# dual-dac-w-32-ch-sh-DAC-BOARD.net
KiCad netlist of a schematic drawn in EAGLE
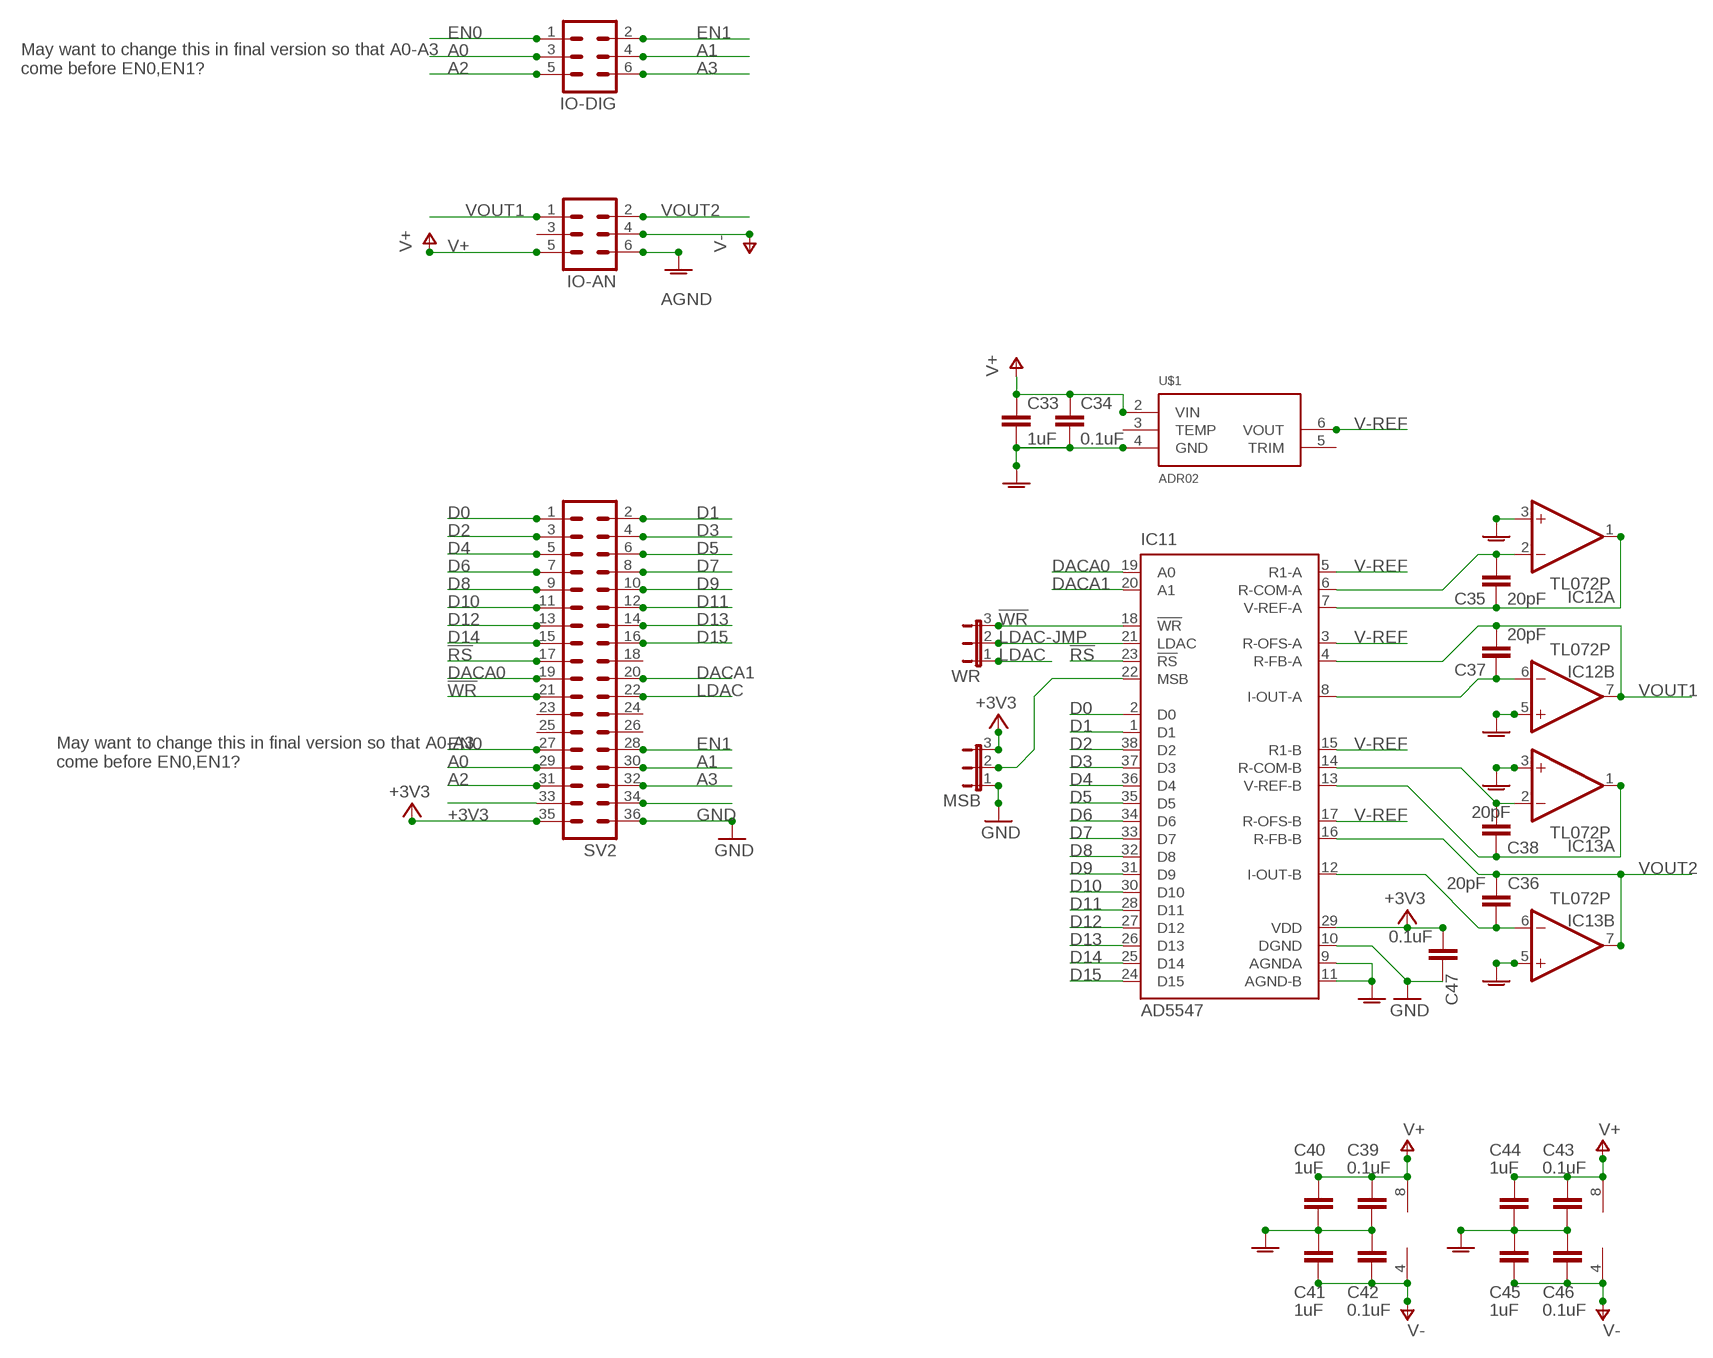
[diagram p0: schematic, sheet 1]

(export (version "E")
  (design (tool "Eeschema 10.0.6"))
  (components
    (comp (ref "C33")
      (value "1uF")
      (footprint "eagle-import:C0603")
      (libsource (lib "eagle-import") (part "C-EUC0603"))
    )
    (comp (ref "C34")
      (value "0.1uF")
      (footprint "eagle-import:C0603")
      (libsource (lib "eagle-import") (part "C-EUC0603"))
    )
    (comp (ref "C35")
      (value "20pF")
      (footprint "eagle-import:C0603")
      (libsource (lib "eagle-import") (part "C-EUC0603"))
    )
    (comp (ref "C36")
      (value "20pF")
      (footprint "eagle-import:C0603")
      (libsource (lib "eagle-import") (part "C-EUC0603"))
    )
    (comp (ref "C37")
      (value "20pF")
      (footprint "eagle-import:C0603")
      (libsource (lib "eagle-import") (part "C-EUC0603"))
    )
    (comp (ref "C38")
      (value "20pF")
      (footprint "eagle-import:C0603")
      (libsource (lib "eagle-import") (part "C-EUC0603"))
    )
    (comp (ref "C39")
      (value "0.1uF")
      (footprint "eagle-import:C0603")
      (libsource (lib "eagle-import") (part "C-EUC0603"))
    )
    (comp (ref "C40")
      (value "1uF")
      (footprint "eagle-import:C0603")
      (libsource (lib "eagle-import") (part "C-EUC0603"))
    )
    (comp (ref "C41")
      (value "1uF")
      (footprint "eagle-import:C0603")
      (libsource (lib "eagle-import") (part "C-EUC0603"))
    )
    (comp (ref "C42")
      (value "0.1uF")
      (footprint "eagle-import:C0603")
      (libsource (lib "eagle-import") (part "C-EUC0603"))
    )
    (comp (ref "C43")
      (value "0.1uF")
      (footprint "eagle-import:C0603")
      (libsource (lib "eagle-import") (part "C-EUC0603"))
    )
    (comp (ref "C44")
      (value "1uF")
      (footprint "eagle-import:C0603")
      (libsource (lib "eagle-import") (part "C-EUC0603"))
    )
    (comp (ref "C45")
      (value "1uF")
      (footprint "eagle-import:C0603")
      (libsource (lib "eagle-import") (part "C-EUC0603"))
    )
    (comp (ref "C46")
      (value "0.1uF")
      (footprint "eagle-import:C0603")
      (libsource (lib "eagle-import") (part "C-EUC0603"))
    )
    (comp (ref "C47")
      (value "0.1uF")
      (footprint "eagle-import:C0603")
      (libsource (lib "eagle-import") (part "C-EUC0603"))
    )
    (comp (ref "IC11")
      (value "AD5547")
      (footprint "eagle-import:TSSOP38")
      (libsource (lib "eagle-import") (part "AD5547"))
    )
    (comp (ref "IC12")
      (value "TL072P")
      (footprint "eagle-import:DIL08")
      (libsource (lib "eagle-import") (part "TL072P"))
    )
    (comp (ref "IC13")
      (value "TL072P")
      (footprint "eagle-import:DIL08")
      (libsource (lib "eagle-import") (part "TL072P"))
    )
    (comp (ref "IO-AN")
      (value "MA03-2")
      (footprint "eagle-import:MA03-2")
      (libsource (lib "eagle-import") (part "MA03-2"))
    )
    (comp (ref "IO-DIG")
      (value "MA03-2")
      (footprint "eagle-import:MA03-2")
      (libsource (lib "eagle-import") (part "MA03-2"))
    )
    (comp (ref "MSB")
      (value "JP2E")
      (footprint "eagle-import:JP2")
      (libsource (lib "eagle-import") (part "JP2E"))
    )
    (comp (ref "SV2")
      (value "MA18-2")
      (footprint "eagle-import:MA18-2")
      (libsource (lib "eagle-import") (part "MA18-2"))
    )
    (comp (ref "U$1")
      (value "ADR02")
      (footprint "eagle-import:SO08")
      (libsource (lib "eagle-import") (part "ADR02"))
    )
    (comp (ref "WR")
      (value "JP2E")
      (footprint "eagle-import:JP2")
      (libsource (lib "eagle-import") (part "JP2E"))
    )
  )
  (nets
    (net (code "1") (name "+3V3") (class "Default")
      (node (ref "C47") (pin "1") (pinfunction "1_1") (pintype "passive"))
      (node (ref "IC11") (pin "29") (pinfunction "VDD_29") (pintype "power_in"))
      (node (ref "MSB") (pin "3") (pinfunction "3_3") (pintype "passive"))
      (node (ref "SV2") (pin "35") (pinfunction "35_35") (pintype "passive"))
    )
    (net (code "2") (name "/A0") (class "Default")
      (node (ref "IO-DIG") (pin "3") (pinfunction "3_3") (pintype "passive"))
      (node (ref "SV2") (pin "29") (pinfunction "29_29") (pintype "passive"))
    )
    (net (code "3") (name "/A1") (class "Default")
      (node (ref "IO-DIG") (pin "4") (pinfunction "4_4") (pintype "passive"))
      (node (ref "SV2") (pin "30") (pinfunction "30_30") (pintype "passive"))
    )
    (net (code "4") (name "/A2") (class "Default")
      (node (ref "IO-DIG") (pin "5") (pinfunction "5_5") (pintype "passive"))
      (node (ref "SV2") (pin "31") (pinfunction "31_31") (pintype "passive"))
    )
    (net (code "5") (name "/A3") (class "Default")
      (node (ref "IO-DIG") (pin "6") (pinfunction "6_6") (pintype "passive"))
      (node (ref "SV2") (pin "32") (pinfunction "32_32") (pintype "passive"))
    )
    (net (code "6") (name "/D0") (class "Default")
      (node (ref "IC11") (pin "2") (pinfunction "D0_2") (pintype "input"))
      (node (ref "SV2") (pin "1") (pinfunction "1_1") (pintype "passive"))
    )
    (net (code "7") (name "/D1") (class "Default")
      (node (ref "IC11") (pin "1") (pinfunction "D1_1") (pintype "input"))
      (node (ref "SV2") (pin "2") (pinfunction "2_2") (pintype "passive"))
    )
    (net (code "8") (name "/D2") (class "Default")
      (node (ref "IC11") (pin "38") (pinfunction "D2_38") (pintype "input"))
      (node (ref "SV2") (pin "3") (pinfunction "3_3") (pintype "passive"))
    )
    (net (code "9") (name "/D3") (class "Default")
      (node (ref "IC11") (pin "37") (pinfunction "D3_37") (pintype "input"))
      (node (ref "SV2") (pin "4") (pinfunction "4_4") (pintype "passive"))
    )
    (net (code "10") (name "/D4") (class "Default")
      (node (ref "IC11") (pin "36") (pinfunction "D4_36") (pintype "input"))
      (node (ref "SV2") (pin "5") (pinfunction "5_5") (pintype "passive"))
    )
    (net (code "11") (name "/D5") (class "Default")
      (node (ref "IC11") (pin "35") (pinfunction "D5_35") (pintype "input"))
      (node (ref "SV2") (pin "6") (pinfunction "6_6") (pintype "passive"))
    )
    (net (code "12") (name "/D6") (class "Default")
      (node (ref "IC11") (pin "34") (pinfunction "D6_34") (pintype "input"))
      (node (ref "SV2") (pin "7") (pinfunction "7_7") (pintype "passive"))
    )
    (net (code "13") (name "/D7") (class "Default")
      (node (ref "IC11") (pin "33") (pinfunction "D7_33") (pintype "input"))
      (node (ref "SV2") (pin "8") (pinfunction "8_8") (pintype "passive"))
    )
    (net (code "14") (name "/D8") (class "Default")
      (node (ref "IC11") (pin "32") (pinfunction "D8_32") (pintype "input"))
      (node (ref "SV2") (pin "9") (pinfunction "9_9") (pintype "passive"))
    )
    (net (code "15") (name "/D9") (class "Default")
      (node (ref "IC11") (pin "31") (pinfunction "D9_31") (pintype "input"))
      (node (ref "SV2") (pin "10") (pinfunction "10_10") (pintype "passive"))
    )
    (net (code "16") (name "/D10") (class "Default")
      (node (ref "IC11") (pin "30") (pinfunction "D10_30") (pintype "input"))
      (node (ref "SV2") (pin "11") (pinfunction "11_11") (pintype "passive"))
    )
    (net (code "17") (name "/D11") (class "Default")
      (node (ref "IC11") (pin "28") (pinfunction "D11_28") (pintype "input"))
      (node (ref "SV2") (pin "12") (pinfunction "12_12") (pintype "passive"))
    )
    (net (code "18") (name "/D12") (class "Default")
      (node (ref "IC11") (pin "27") (pinfunction "D12_27") (pintype "input"))
      (node (ref "SV2") (pin "13") (pinfunction "13_13") (pintype "passive"))
    )
    (net (code "19") (name "/D13") (class "Default")
      (node (ref "IC11") (pin "26") (pinfunction "D13_26") (pintype "input"))
      (node (ref "SV2") (pin "14") (pinfunction "14_14") (pintype "passive"))
    )
    (net (code "20") (name "/D14") (class "Default")
      (node (ref "IC11") (pin "25") (pinfunction "D14_25") (pintype "input"))
      (node (ref "SV2") (pin "15") (pinfunction "15_15") (pintype "passive"))
    )
    (net (code "21") (name "/D15") (class "Default")
      (node (ref "IC11") (pin "24") (pinfunction "D15_24") (pintype "input"))
      (node (ref "SV2") (pin "16") (pinfunction "16_16") (pintype "passive"))
    )
    (net (code "22") (name "/DACA0") (class "Default")
      (node (ref "IC11") (pin "19") (pinfunction "A0_19") (pintype "input"))
      (node (ref "SV2") (pin "19") (pinfunction "19_19") (pintype "passive"))
    )
    (net (code "23") (name "/DACA1") (class "Default")
      (node (ref "IC11") (pin "20") (pinfunction "A1_20") (pintype "input"))
      (node (ref "SV2") (pin "20") (pinfunction "20_20") (pintype "passive"))
    )
    (net (code "24") (name "/EN0") (class "Default")
      (node (ref "IO-DIG") (pin "1") (pinfunction "1_1") (pintype "passive"))
      (node (ref "SV2") (pin "27") (pinfunction "27_27") (pintype "passive"))
    )
    (net (code "25") (name "/EN1") (class "Default")
      (node (ref "IO-DIG") (pin "2") (pinfunction "2_2") (pintype "passive"))
      (node (ref "SV2") (pin "28") (pinfunction "28_28") (pintype "passive"))
    )
    (net (code "26") (name "/LDAC") (class "Default")
      (node (ref "SV2") (pin "22") (pinfunction "22_22") (pintype "passive"))
      (node (ref "WR") (pin "1") (pinfunction "1_1") (pintype "passive"))
    )
    (net (code "27") (name "/LDAC-JMP") (class "Default")
      (node (ref "IC11") (pin "21") (pinfunction "LDAC_21") (pintype "input"))
      (node (ref "WR") (pin "2") (pinfunction "2_2") (pintype "passive"))
    )
    (net (code "28") (name "/V-REF") (class "Default")
      (node (ref "IC11") (pin "15") (pinfunction "R1-B_15") (pintype "input"))
      (node (ref "IC11") (pin "17") (pinfunction "R-OFS-B_17") (pintype "input"))
      (node (ref "IC11") (pin "3") (pinfunction "R-OFS-A_3") (pintype "input"))
      (node (ref "IC11") (pin "5") (pinfunction "R1-A_5") (pintype "input"))
      (node (ref "U$1") (pin "6") (pinfunction "VOUT_6") (pintype "output"))
    )
    (net (code "29") (name "/VOUT1") (class "Default")
      (node (ref "C37") (pin "1") (pinfunction "1_1") (pintype "passive"))
      (node (ref "IC11") (pin "4") (pinfunction "R-FB-A_4") (pintype "input"))
      (node (ref "IC12") (pin "7") (pinfunction "OUT_7") (pintype "output"))
      (node (ref "IO-AN") (pin "1") (pinfunction "1_1") (pintype "passive"))
    )
    (net (code "30") (name "/VOUT2") (class "Default")
      (node (ref "C36") (pin "1") (pinfunction "1_1") (pintype "passive"))
      (node (ref "IC11") (pin "16") (pinfunction "R-FB-B_16") (pintype "input"))
      (node (ref "IC13") (pin "7") (pinfunction "OUT_7") (pintype "output"))
      (node (ref "IO-AN") (pin "2") (pinfunction "2_2") (pintype "passive"))
    )
    (net (code "31") (name "/~{RS}") (class "Default")
      (node (ref "IC11") (pin "23") (pinfunction "~{RS}_23") (pintype "input"))
      (node (ref "SV2") (pin "17") (pinfunction "17_17") (pintype "passive"))
    )
    (net (code "32") (name "/~{WR}") (class "Default")
      (node (ref "IC11") (pin "18") (pinfunction "~{WR}_18") (pintype "input"))
      (node (ref "SV2") (pin "21") (pinfunction "21_21") (pintype "passive"))
      (node (ref "WR") (pin "3") (pinfunction "3_3") (pintype "passive"))
    )
    (net (code "33") (name "AGND") (class "Default")
      (node (ref "C33") (pin "2") (pinfunction "2_2") (pintype "passive"))
      (node (ref "C34") (pin "2") (pinfunction "2_2") (pintype "passive"))
      (node (ref "C39") (pin "1") (pinfunction "1_1") (pintype "passive"))
      (node (ref "C40") (pin "1") (pinfunction "1_1") (pintype "passive"))
      (node (ref "C41") (pin "2") (pinfunction "2_2") (pintype "passive"))
      (node (ref "C42") (pin "2") (pinfunction "2_2") (pintype "passive"))
      (node (ref "C43") (pin "1") (pinfunction "1_1") (pintype "passive"))
      (node (ref "C44") (pin "1") (pinfunction "1_1") (pintype "passive"))
      (node (ref "C45") (pin "2") (pinfunction "2_2") (pintype "passive"))
      (node (ref "C46") (pin "2") (pinfunction "2_2") (pintype "passive"))
      (node (ref "IC11") (pin "11") (pinfunction "AGND-B_11") (pintype "input"))
      (node (ref "IC11") (pin "9") (pinfunction "AGNDA_9") (pintype "input"))
      (node (ref "IC12") (pin "3") (pinfunction "+IN_3") (pintype "input"))
      (node (ref "IC12") (pin "5") (pinfunction "+IN_5") (pintype "input"))
      (node (ref "IC13") (pin "3") (pinfunction "+IN_3") (pintype "input"))
      (node (ref "IC13") (pin "5") (pinfunction "+IN_5") (pintype "input"))
      (node (ref "IO-AN") (pin "6") (pinfunction "6_6") (pintype "passive"))
      (node (ref "U$1") (pin "4") (pinfunction "GND_4") (pintype "input"))
    )
    (net (code "34") (name "GND") (class "Default")
      (node (ref "C47") (pin "2") (pinfunction "2_2") (pintype "passive"))
      (node (ref "IC11") (pin "10") (pinfunction "DGND_10") (pintype "input"))
      (node (ref "MSB") (pin "1") (pinfunction "1_1") (pintype "passive"))
      (node (ref "SV2") (pin "36") (pinfunction "36_36") (pintype "passive"))
    )
    (net (code "35") (name "Net-(IC11-I-OUT-A)") (class "Default")
      (node (ref "C37") (pin "2") (pinfunction "2_2") (pintype "passive"))
      (node (ref "IC11") (pin "8") (pinfunction "I-OUT-A_8") (pintype "output"))
      (node (ref "IC12") (pin "6") (pinfunction "-IN_6") (pintype "input"))
    )
    (net (code "36") (name "Net-(IC11-I-OUT-B)") (class "Default")
      (node (ref "C36") (pin "2") (pinfunction "2_2") (pintype "passive"))
      (node (ref "IC11") (pin "12") (pinfunction "I-OUT-B_12") (pintype "output"))
      (node (ref "IC13") (pin "6") (pinfunction "-IN_6") (pintype "input"))
    )
    (net (code "37") (name "Net-(IC11-MSB)") (class "Default")
      (node (ref "IC11") (pin "22") (pinfunction "MSB_22") (pintype "input"))
      (node (ref "MSB") (pin "2") (pinfunction "2_2") (pintype "passive"))
    )
    (net (code "38") (name "Net-(IC11-R-COM-A)") (class "Default")
      (node (ref "C35") (pin "2") (pinfunction "2_2") (pintype "passive"))
      (node (ref "IC11") (pin "6") (pinfunction "R-COM-A_6") (pintype "bidirectional"))
      (node (ref "IC12") (pin "2") (pinfunction "-IN_2") (pintype "input"))
    )
    (net (code "39") (name "Net-(IC11-R-COM-B)") (class "Default")
      (node (ref "C38") (pin "2") (pinfunction "2_2") (pintype "passive"))
      (node (ref "IC11") (pin "14") (pinfunction "R-COM-B_14") (pintype "bidirectional"))
      (node (ref "IC13") (pin "2") (pinfunction "-IN_2") (pintype "input"))
    )
    (net (code "40") (name "Net-(IC11-V-REF-A)") (class "Default")
      (node (ref "C35") (pin "1") (pinfunction "1_1") (pintype "passive"))
      (node (ref "IC11") (pin "7") (pinfunction "V-REF-A_7") (pintype "input"))
      (node (ref "IC12") (pin "1") (pinfunction "OUT_1") (pintype "output"))
    )
    (net (code "41") (name "Net-(IC11-V-REF-B)") (class "Default")
      (node (ref "C38") (pin "1") (pinfunction "1_1") (pintype "passive"))
      (node (ref "IC11") (pin "13") (pinfunction "V-REF-B_13") (pintype "input"))
      (node (ref "IC13") (pin "1") (pinfunction "OUT_1") (pintype "output"))
    )
    (net (code "42") (name "V+") (class "Default")
      (node (ref "C33") (pin "1") (pinfunction "1_1") (pintype "passive"))
      (node (ref "C34") (pin "1") (pinfunction "1_1") (pintype "passive"))
      (node (ref "C39") (pin "2") (pinfunction "2_2") (pintype "passive"))
      (node (ref "C40") (pin "2") (pinfunction "2_2") (pintype "passive"))
      (node (ref "C43") (pin "2") (pinfunction "2_2") (pintype "passive"))
      (node (ref "C44") (pin "2") (pinfunction "2_2") (pintype "passive"))
      (node (ref "IC12") (pin "8") (pinfunction "V+_8") (pintype "power_in"))
      (node (ref "IC13") (pin "8") (pinfunction "V+_8") (pintype "power_in"))
      (node (ref "IO-AN") (pin "5") (pinfunction "5_5") (pintype "passive"))
      (node (ref "U$1") (pin "2") (pinfunction "VIN_2") (pintype "power_in"))
    )
    (net (code "43") (name "V-") (class "Default")
      (node (ref "C41") (pin "1") (pinfunction "1_1") (pintype "passive"))
      (node (ref "C42") (pin "1") (pinfunction "1_1") (pintype "passive"))
      (node (ref "C45") (pin "1") (pinfunction "1_1") (pintype "passive"))
      (node (ref "C46") (pin "1") (pinfunction "1_1") (pintype "passive"))
      (node (ref "IC12") (pin "4") (pinfunction "V-_4") (pintype "power_in"))
      (node (ref "IC13") (pin "4") (pinfunction "V-_4") (pintype "power_in"))
      (node (ref "IO-AN") (pin "4") (pinfunction "4_4") (pintype "passive"))
    )
    (net (code "44") (name "unconnected-(IO-AN-Pad3)") (class "Default")
      (node (ref "IO-AN") (pin "3") (pinfunction "3_3") (pintype "passive"))
    )
    (net (code "45") (name "unconnected-(SV2-Pad18)") (class "Default")
      (node (ref "SV2") (pin "18") (pinfunction "18_18") (pintype "passive"))
    )
    (net (code "46") (name "unconnected-(SV2-Pad23)") (class "Default")
      (node (ref "SV2") (pin "23") (pinfunction "23_23") (pintype "passive"))
    )
    (net (code "47") (name "unconnected-(SV2-Pad24)") (class "Default")
      (node (ref "SV2") (pin "24") (pinfunction "24_24") (pintype "passive"))
    )
    (net (code "48") (name "unconnected-(SV2-Pad25)") (class "Default")
      (node (ref "SV2") (pin "25") (pinfunction "25_25") (pintype "passive"))
    )
    (net (code "49") (name "unconnected-(SV2-Pad26)") (class "Default")
      (node (ref "SV2") (pin "26") (pinfunction "26_26") (pintype "passive"))
    )
    (net (code "50") (name "unconnected-(SV2-Pad33)") (class "Default")
      (node (ref "SV2") (pin "33") (pinfunction "33_33") (pintype "passive"))
    )
    (net (code "51") (name "unconnected-(SV2-Pad34)") (class "Default")
      (node (ref "SV2") (pin "34") (pinfunction "34_34") (pintype "passive"))
    )
    (net (code "52") (name "unconnected-(U$1-TEMP-Pad3)") (class "Default")
      (node (ref "U$1") (pin "3") (pinfunction "TEMP_3") (pintype "input"))
    )
    (net (code "53") (name "unconnected-(U$1-TRIM-Pad5)") (class "Default")
      (node (ref "U$1") (pin "5") (pinfunction "TRIM_5") (pintype "input"))
    )
  )
)
